# 32U4Castel.net
KiCad netlist of a schematic drawn in EAGLE
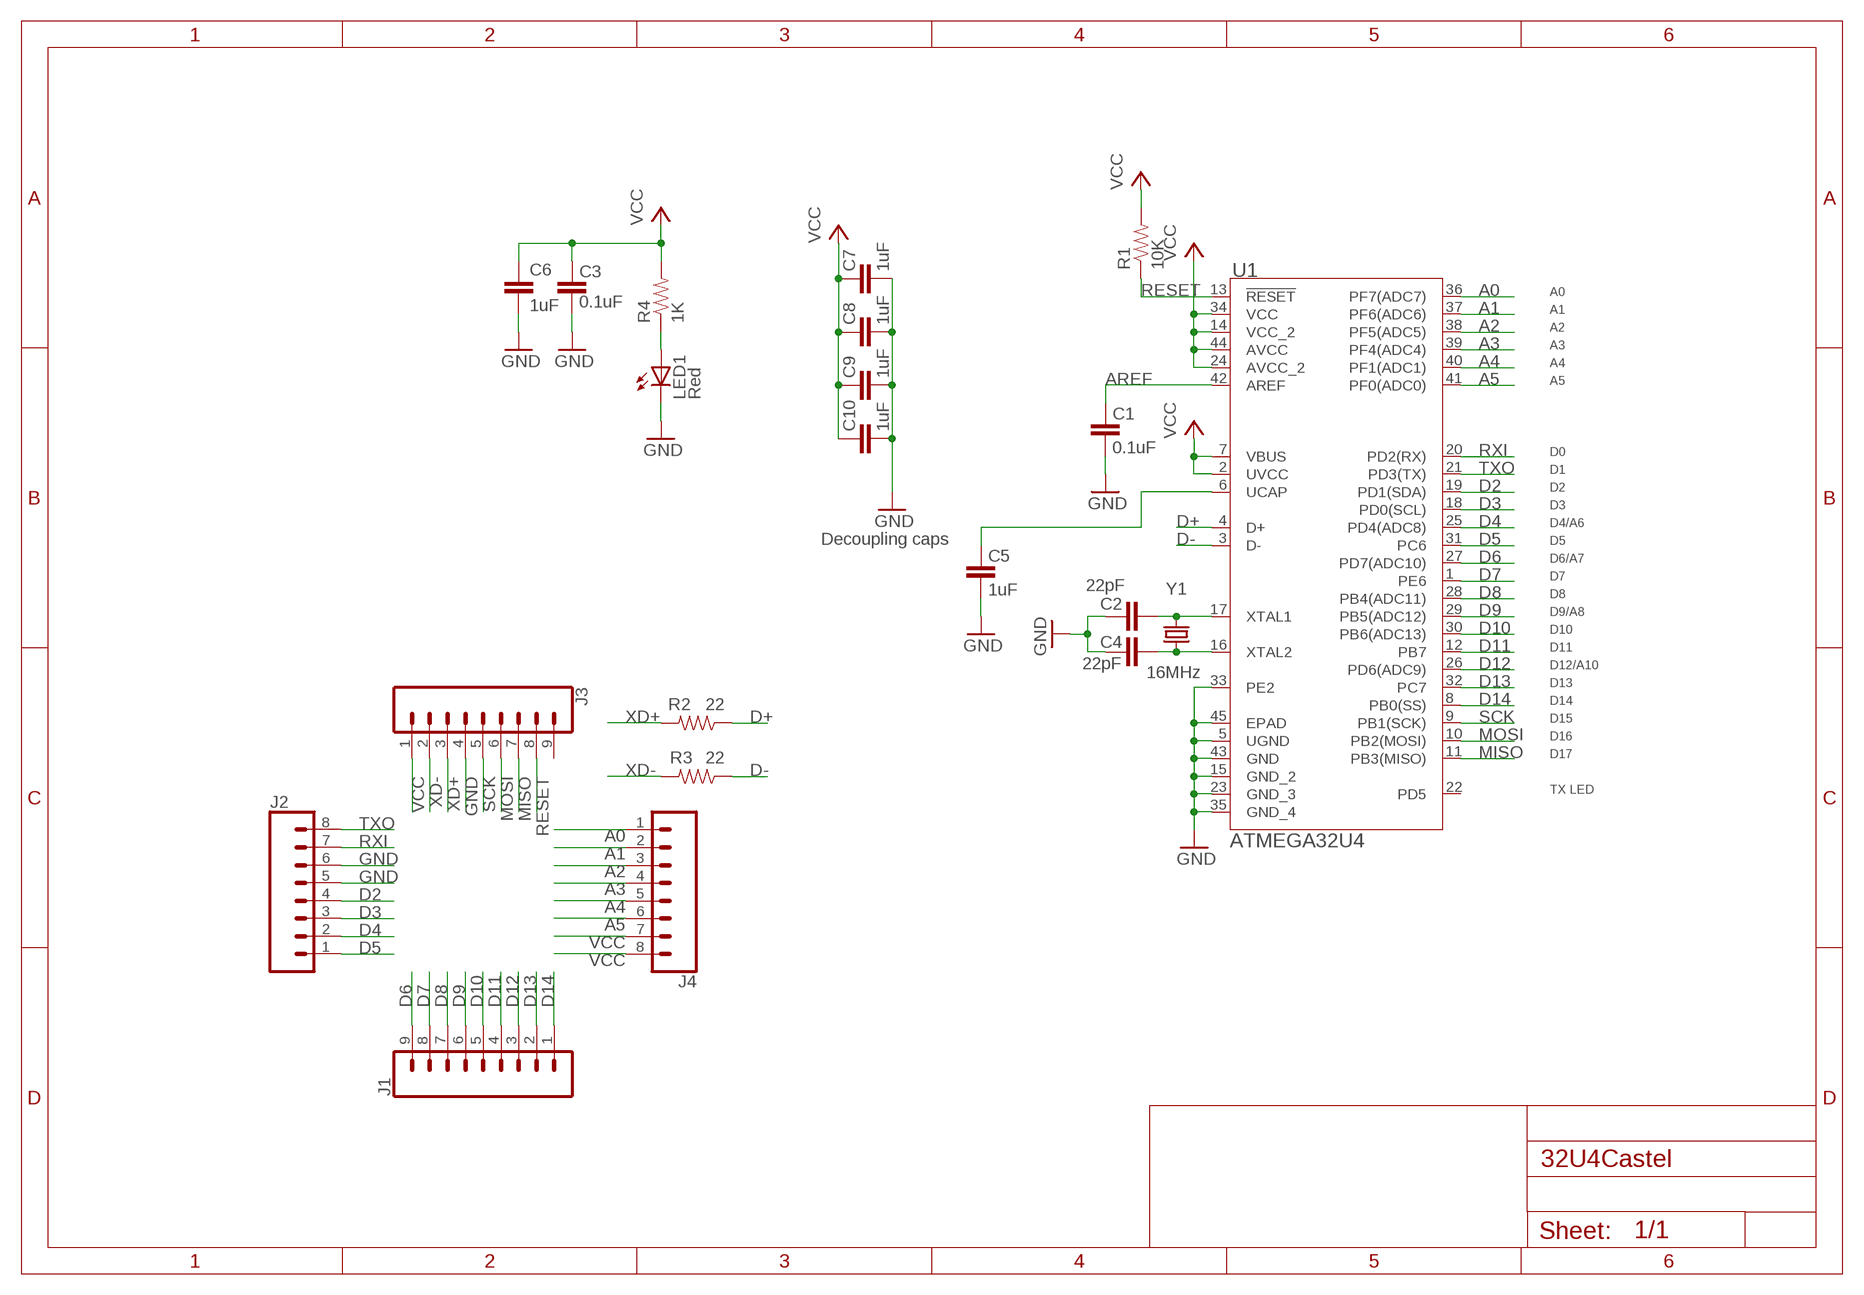
[diagram p0: schematic, sheet 1]

(export (version "E")
  (design (tool "Eeschema 10.0.6"))
  (components
    (comp (ref "C1")
      (value "0.1uF")
      (footprint "eagle-import:0603-CAP")
      (libsource (lib "eagle-import") (part "CAP0603-CAP"))
    )
    (comp (ref "C2")
      (value "22pF")
      (footprint "eagle-import:0603-CAP")
      (libsource (lib "eagle-import") (part "CAP0603-CAP"))
    )
    (comp (ref "C3")
      (value "0.1uF")
      (footprint "eagle-import:0603-CAP")
      (libsource (lib "eagle-import") (part "CAP0603-CAP"))
    )
    (comp (ref "C4")
      (value "22pF")
      (footprint "eagle-import:0603-CAP")
      (libsource (lib "eagle-import") (part "CAP0603-CAP"))
    )
    (comp (ref "C5")
      (value "1uF")
      (footprint "eagle-import:0603-CAP")
      (libsource (lib "eagle-import") (part "CAP0603-CAP"))
    )
    (comp (ref "C6")
      (value "1uF")
      (footprint "eagle-import:0603-CAP")
      (libsource (lib "eagle-import") (part "CAP0603-CAP"))
    )
    (comp (ref "C7")
      (value "1uF")
      (footprint "eagle-import:0603-CAP")
      (libsource (lib "eagle-import") (part "CAP0603-CAP"))
    )
    (comp (ref "C8")
      (value "1uF")
      (footprint "eagle-import:0603-CAP")
      (libsource (lib "eagle-import") (part "CAP0603-CAP"))
    )
    (comp (ref "C9")
      (value "1uF")
      (footprint "eagle-import:0603-CAP")
      (libsource (lib "eagle-import") (part "CAP0603-CAP"))
    )
    (comp (ref "C10")
      (value "1uF")
      (footprint "eagle-import:0603-CAP")
      (libsource (lib "eagle-import") (part "CAP0603-CAP"))
    )
    (comp (ref "J1")
      (value "CONN_09NO_SILK")
      (footprint "eagle-import:1X09_NO_SILK")
      (libsource (lib "eagle-import") (part "CONN_09NO_SILK"))
    )
    (comp (ref "J2")
      (value "CONN_08NO_SILK_FEMALE_PTH")
      (footprint "eagle-import:1X08_NO_SILK")
      (libsource (lib "eagle-import") (part "CONN_08NO_SILK_FEMALE_PTH"))
    )
    (comp (ref "J3")
      (value "CONN_09NO_SILK")
      (footprint "eagle-import:1X09_NO_SILK")
      (libsource (lib "eagle-import") (part "CONN_09NO_SILK"))
    )
    (comp (ref "J4")
      (value "CONN_08NO_SILK_FEMALE_PTH")
      (footprint "eagle-import:1X08_NO_SILK")
      (libsource (lib "eagle-import") (part "CONN_08NO_SILK_FEMALE_PTH"))
    )
    (comp (ref "LED1")
      (value "Red")
      (footprint "eagle-import:LED-0603")
      (libsource (lib "eagle-import") (part "LED0603"))
    )
    (comp (ref "R1")
      (value "10K")
      (footprint "eagle-import:0603-RES")
      (libsource (lib "eagle-import") (part "RESISTOR0603-RES"))
    )
    (comp (ref "R2")
      (value "22")
      (footprint "eagle-import:0603-RES")
      (libsource (lib "eagle-import") (part "RESISTOR0603-RES"))
    )
    (comp (ref "R3")
      (value "22")
      (footprint "eagle-import:0603-RES")
      (libsource (lib "eagle-import") (part "RESISTOR0603-RES"))
    )
    (comp (ref "R4")
      (value "1K")
      (footprint "eagle-import:0603-RES")
      (libsource (lib "eagle-import") (part "RESISTOR0603-RES"))
    )
    (comp (ref "U1")
      (value "ATMEGA32U4-MU")
      (footprint "eagle-import:44PW")
      (fields (field (name "MANUFACTURER_PART_NUMBER") "ATMEGA32U4MU"))
      (libsource (lib "eagle-import") (part "ATMEGA32U4-MU"))
    )
    (comp (ref "Y1")
      (value "16MHz")
      (footprint "eagle-import:CRYSTAL-SMD-5X3")
      (libsource (lib "eagle-import") (part "CRYSTAL5X3"))
    )
  )
  (nets
    (net (code "1") (name "/A0") (class "Default")
      (node (ref "J4") (pin "1") (pinfunction "1_1") (pintype "passive"))
      (node (ref "U1") (pin "36") (pinfunction "PF7(ADC7)_36") (pintype "bidirectional"))
    )
    (net (code "2") (name "/A1") (class "Default")
      (node (ref "J4") (pin "2") (pinfunction "2_2") (pintype "passive"))
      (node (ref "U1") (pin "37") (pinfunction "PF6(ADC6)_37") (pintype "bidirectional"))
    )
    (net (code "3") (name "/A2") (class "Default")
      (node (ref "J4") (pin "3") (pinfunction "3_3") (pintype "passive"))
      (node (ref "U1") (pin "38") (pinfunction "PF5(ADC5)_38") (pintype "bidirectional"))
    )
    (net (code "4") (name "/A3") (class "Default")
      (node (ref "J4") (pin "4") (pinfunction "4_4") (pintype "passive"))
      (node (ref "U1") (pin "39") (pinfunction "PF4(ADC4)_39") (pintype "bidirectional"))
    )
    (net (code "5") (name "/A4") (class "Default")
      (node (ref "J4") (pin "5") (pinfunction "5_5") (pintype "passive"))
      (node (ref "U1") (pin "40") (pinfunction "PF1(ADC1)_40") (pintype "bidirectional"))
    )
    (net (code "6") (name "/A5") (class "Default")
      (node (ref "J4") (pin "6") (pinfunction "6_6") (pintype "passive"))
      (node (ref "U1") (pin "41") (pinfunction "PF0(ADC0)_41") (pintype "bidirectional"))
    )
    (net (code "7") (name "/AREF") (class "Default")
      (node (ref "C1") (pin "2") (pinfunction "2_2") (pintype "passive"))
      (node (ref "U1") (pin "42") (pinfunction "AREF_42") (pintype "input"))
    )
    (net (code "8") (name "/D+") (class "Default")
      (node (ref "R2") (pin "1") (pinfunction "1_1") (pintype "passive"))
      (node (ref "U1") (pin "4") (pinfunction "D+_4") (pintype "passive"))
    )
    (net (code "9") (name "/D-") (class "Default")
      (node (ref "R3") (pin "1") (pinfunction "1_1") (pintype "passive"))
      (node (ref "U1") (pin "3") (pinfunction "D-_3") (pintype "passive"))
    )
    (net (code "10") (name "/D2") (class "Default")
      (node (ref "J2") (pin "4") (pinfunction "4_4") (pintype "passive"))
      (node (ref "U1") (pin "19") (pinfunction "PD1(SDA)_19") (pintype "bidirectional"))
    )
    (net (code "11") (name "/D3") (class "Default")
      (node (ref "J2") (pin "3") (pinfunction "3_3") (pintype "passive"))
      (node (ref "U1") (pin "18") (pinfunction "PD0(SCL)_18") (pintype "bidirectional"))
    )
    (net (code "12") (name "/D4") (class "Default")
      (node (ref "J2") (pin "2") (pinfunction "2_2") (pintype "passive"))
      (node (ref "U1") (pin "25") (pinfunction "PD4(ADC8)_25") (pintype "bidirectional"))
    )
    (net (code "13") (name "/D5") (class "Default")
      (node (ref "J2") (pin "1") (pinfunction "1_1") (pintype "passive"))
      (node (ref "U1") (pin "31") (pinfunction "PC6_31") (pintype "bidirectional"))
    )
    (net (code "14") (name "/D6") (class "Default")
      (node (ref "J1") (pin "9") (pinfunction "9_9") (pintype "passive"))
      (node (ref "U1") (pin "27") (pinfunction "PD7(ADC10)_27") (pintype "bidirectional"))
    )
    (net (code "15") (name "/D7") (class "Default")
      (node (ref "J1") (pin "8") (pinfunction "8_8") (pintype "passive"))
      (node (ref "U1") (pin "1") (pinfunction "PE6_1") (pintype "bidirectional"))
    )
    (net (code "16") (name "/D8") (class "Default")
      (node (ref "J1") (pin "7") (pinfunction "7_7") (pintype "passive"))
      (node (ref "U1") (pin "28") (pinfunction "PB4(ADC11)_28") (pintype "bidirectional"))
    )
    (net (code "17") (name "/D9") (class "Default")
      (node (ref "J1") (pin "6") (pinfunction "6_6") (pintype "passive"))
      (node (ref "U1") (pin "29") (pinfunction "PB5(ADC12)_29") (pintype "bidirectional"))
    )
    (net (code "18") (name "/D10") (class "Default")
      (node (ref "J1") (pin "5") (pinfunction "5_5") (pintype "passive"))
      (node (ref "U1") (pin "30") (pinfunction "PB6(ADC13)_30") (pintype "bidirectional"))
    )
    (net (code "19") (name "/D11") (class "Default")
      (node (ref "J1") (pin "4") (pinfunction "4_4") (pintype "passive"))
      (node (ref "U1") (pin "12") (pinfunction "PB7_12") (pintype "bidirectional"))
    )
    (net (code "20") (name "/D12") (class "Default")
      (node (ref "J1") (pin "3") (pinfunction "3_3") (pintype "passive"))
      (node (ref "U1") (pin "26") (pinfunction "PD6(ADC9)_26") (pintype "bidirectional"))
    )
    (net (code "21") (name "/D13") (class "Default")
      (node (ref "J1") (pin "2") (pinfunction "2_2") (pintype "passive"))
      (node (ref "U1") (pin "32") (pinfunction "PC7_32") (pintype "bidirectional"))
    )
    (net (code "22") (name "/D14") (class "Default")
      (node (ref "J1") (pin "1") (pinfunction "1_1") (pintype "passive"))
      (node (ref "U1") (pin "8") (pinfunction "PB0(SS)_8") (pintype "bidirectional"))
    )
    (net (code "23") (name "/MISO") (class "Default")
      (node (ref "J3") (pin "7") (pinfunction "7_7") (pintype "passive"))
      (node (ref "U1") (pin "11") (pinfunction "PB3(MISO)_11") (pintype "bidirectional"))
    )
    (net (code "24") (name "/MOSI") (class "Default")
      (node (ref "J3") (pin "6") (pinfunction "6_6") (pintype "passive"))
      (node (ref "U1") (pin "10") (pinfunction "PB2(MOSI)_10") (pintype "bidirectional"))
    )
    (net (code "25") (name "/RESET") (class "Default")
      (node (ref "J3") (pin "8") (pinfunction "8_8") (pintype "passive"))
      (node (ref "R1") (pin "1") (pinfunction "1_1") (pintype "passive"))
      (node (ref "U1") (pin "13") (pinfunction "~{RESET}_13") (pintype "input"))
    )
    (net (code "26") (name "/RXI") (class "Default")
      (node (ref "J2") (pin "7") (pinfunction "7_7") (pintype "passive"))
      (node (ref "U1") (pin "20") (pinfunction "PD2(RX)_20") (pintype "bidirectional"))
    )
    (net (code "27") (name "/SCK") (class "Default")
      (node (ref "J3") (pin "5") (pinfunction "5_5") (pintype "passive"))
      (node (ref "U1") (pin "9") (pinfunction "PB1(SCK)_9") (pintype "bidirectional"))
    )
    (net (code "28") (name "/TXO") (class "Default")
      (node (ref "J2") (pin "8") (pinfunction "8_8") (pintype "passive"))
      (node (ref "U1") (pin "21") (pinfunction "PD3(TX)_21") (pintype "bidirectional"))
    )
    (net (code "29") (name "/XD+") (class "Default")
      (node (ref "J3") (pin "3") (pinfunction "3_3") (pintype "passive"))
      (node (ref "R2") (pin "2") (pinfunction "2_2") (pintype "passive"))
    )
    (net (code "30") (name "/XD-") (class "Default")
      (node (ref "J3") (pin "2") (pinfunction "2_2") (pintype "passive"))
      (node (ref "R3") (pin "2") (pinfunction "2_2") (pintype "passive"))
    )
    (net (code "31") (name "GND") (class "Default")
      (node (ref "C1") (pin "1") (pinfunction "1_1") (pintype "passive"))
      (node (ref "C10") (pin "1") (pinfunction "1_1") (pintype "passive"))
      (node (ref "C2") (pin "2") (pinfunction "2_2") (pintype "passive"))
      (node (ref "C3") (pin "1") (pinfunction "1_1") (pintype "passive"))
      (node (ref "C4") (pin "2") (pinfunction "2_2") (pintype "passive"))
      (node (ref "C5") (pin "1") (pinfunction "1_1") (pintype "passive"))
      (node (ref "C6") (pin "2") (pinfunction "2_2") (pintype "passive"))
      (node (ref "C7") (pin "1") (pinfunction "1_1") (pintype "passive"))
      (node (ref "C8") (pin "1") (pinfunction "1_1") (pintype "passive"))
      (node (ref "C9") (pin "1") (pinfunction "1_1") (pintype "passive"))
      (node (ref "J2") (pin "5") (pinfunction "5_5") (pintype "passive"))
      (node (ref "J2") (pin "6") (pinfunction "6_6") (pintype "passive"))
      (node (ref "J3") (pin "4") (pinfunction "4_4") (pintype "passive"))
      (node (ref "LED1") (pin "C") (pinfunction "C_C") (pintype "passive"))
      (node (ref "U1") (pin "15") (pinfunction "GND_2_15") (pintype "power_in"))
      (node (ref "U1") (pin "23") (pinfunction "GND_3_23") (pintype "power_in"))
      (node (ref "U1") (pin "33") (pinfunction "PE2_33") (pintype "bidirectional"))
      (node (ref "U1") (pin "35") (pinfunction "GND_4_35") (pintype "power_in"))
      (node (ref "U1") (pin "43") (pinfunction "GND_43") (pintype "power_in"))
      (node (ref "U1") (pin "45") (pinfunction "EPAD_45") (pintype "passive"))
      (node (ref "U1") (pin "5") (pinfunction "UGND_5") (pintype "power_in"))
    )
    (net (code "32") (name "Net-(LED1-PadA)") (class "Default")
      (node (ref "LED1") (pin "A") (pinfunction "A_A") (pintype "passive"))
      (node (ref "R4") (pin "1") (pinfunction "1_1") (pintype "passive"))
    )
    (net (code "33") (name "Net-(U1-UCAP)") (class "Default")
      (node (ref "C5") (pin "2") (pinfunction "2_2") (pintype "passive"))
      (node (ref "U1") (pin "6") (pinfunction "UCAP_6") (pintype "output"))
    )
    (net (code "34") (name "Net-(U1-XTAL1)") (class "Default")
      (node (ref "C2") (pin "1") (pinfunction "1_1") (pintype "passive"))
      (node (ref "U1") (pin "17") (pinfunction "XTAL1_17") (pintype "input"))
      (node (ref "Y1") (pin "3") (pinfunction "2_3") (pintype "passive"))
    )
    (net (code "35") (name "Net-(U1-XTAL2)") (class "Default")
      (node (ref "C4") (pin "1") (pinfunction "1_1") (pintype "passive"))
      (node (ref "U1") (pin "16") (pinfunction "XTAL2_16") (pintype "output"))
      (node (ref "Y1") (pin "1") (pinfunction "1_1") (pintype "passive"))
    )
    (net (code "36") (name "VCC") (class "Default")
      (node (ref "C10") (pin "2") (pinfunction "2_2") (pintype "passive"))
      (node (ref "C3") (pin "2") (pinfunction "2_2") (pintype "passive"))
      (node (ref "C6") (pin "1") (pinfunction "1_1") (pintype "passive"))
      (node (ref "C7") (pin "2") (pinfunction "2_2") (pintype "passive"))
      (node (ref "C8") (pin "2") (pinfunction "2_2") (pintype "passive"))
      (node (ref "C9") (pin "2") (pinfunction "2_2") (pintype "passive"))
      (node (ref "J3") (pin "1") (pinfunction "1_1") (pintype "passive"))
      (node (ref "J4") (pin "7") (pinfunction "7_7") (pintype "passive"))
      (node (ref "J4") (pin "8") (pinfunction "8_8") (pintype "passive"))
      (node (ref "R1") (pin "2") (pinfunction "2_2") (pintype "passive"))
      (node (ref "R4") (pin "2") (pinfunction "2_2") (pintype "passive"))
      (node (ref "U1") (pin "14") (pinfunction "VCC_2_14") (pintype "power_in"))
      (node (ref "U1") (pin "2") (pinfunction "UVCC_2") (pintype "power_in"))
      (node (ref "U1") (pin "24") (pinfunction "AVCC_2_24") (pintype "power_in"))
      (node (ref "U1") (pin "34") (pinfunction "VCC_34") (pintype "power_in"))
      (node (ref "U1") (pin "44") (pinfunction "AVCC_44") (pintype "power_in"))
      (node (ref "U1") (pin "7") (pinfunction "VBUS_7") (pintype "input"))
    )
    (net (code "37") (name "unconnected-(J3-Pad9)") (class "Default")
      (node (ref "J3") (pin "9") (pinfunction "9_9") (pintype "passive"))
    )
    (net (code "38") (name "unconnected-(U1-PD5-Pad22)") (class "Default")
      (node (ref "U1") (pin "22") (pinfunction "PD5_22") (pintype "bidirectional"))
    )
  )
)
